# Power.net
KiCad netlist of a schematic drawn in Altium Designer
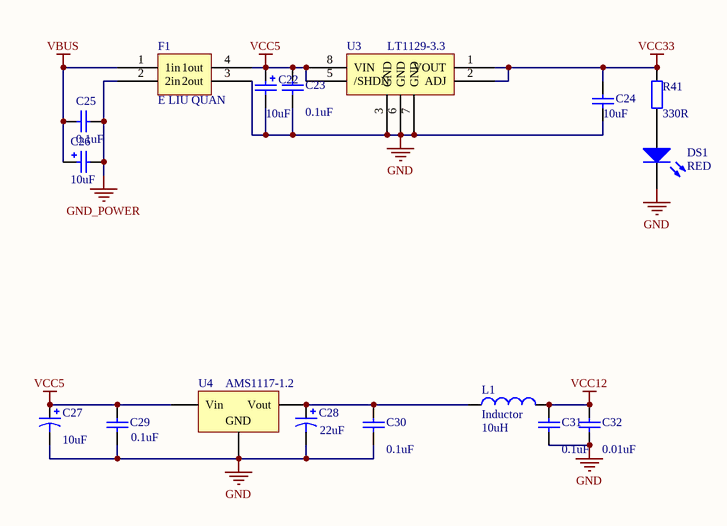
[diagram p0: Power.SchDoc]

(export (version "E")
  (design (tool "Eeschema 10.0.6"))
  (components
    (comp (ref "C22")
      (value "10uF")
      (footprint "cc0603")
      (description "Polarized Capacitor (Radial)")
      (fields (field (name "PUBLISHER") "Altium Limited"))
      (libsource (lib "") (part "Cap Pol1_1"))
    )
    (comp (ref "C23")
      (value "0.1uF")
      (footprint "cc0603")
      (description "Capacitor")
      (fields (field (name "PUBLISHER") "Altium Limited"))
      (libsource (lib "Miscellaneous Devices") (part "Cap"))
    )
    (comp (ref "C24")
      (value "10uF")
      (footprint "cc0603")
      (description "Capacitor")
      (fields (field (name "PUBLISHER") "Altium Limited"))
      (libsource (lib "Miscellaneous Devices") (part "Cap"))
    )
    (comp (ref "C25")
      (value "0.1uF")
      (footprint "cc0603")
      (description "Capacitor")
      (fields (field (name "PUBLISHER") "Altium Limited"))
      (libsource (lib "Miscellaneous Devices") (part "Cap"))
    )
    (comp (ref "C26")
      (value "10uF")
      (footprint "CC6332-2512")
      (description "Polarized Capacitor (Radial)")
      (fields (field (name "PUBLISHER") "Altium Limited"))
      (libsource (lib "") (part "Cap Pol1_1"))
    )
    (comp (ref "C27")
      (value "10uF")
      (footprint "CC6332-2512")
      (description "Polarized Capacitor (Radial)")
      (fields (field (name "PUBLISHER") "Altium Limited"))
      (libsource (lib "Miscellaneous Devices") (part "Cap Pol1"))
    )
    (comp (ref "C28")
      (value "22uF")
      (footprint "CC6332-2512")
      (description "Polarized Capacitor (Radial)")
      (fields (field (name "Comment") "Cap Pol1") (field (name "PUBLISHER") "Altium Limited"))
      (libsource (lib "Miscellaneous Devices") (part "Cap Pol1"))
    )
    (comp (ref "C29")
      (value "0.1uF")
      (footprint "cc0603")
      (description "Capacitor")
      (fields (field (name "PUBLISHER") "Altium Limited"))
      (libsource (lib "Miscellaneous Devices") (part "Cap"))
    )
    (comp (ref "C30")
      (value "0.1uF")
      (footprint "cc0603")
      (description "Capacitor")
      (fields (field (name "PUBLISHER") "Altium Limited"))
      (libsource (lib "Miscellaneous Devices") (part "Cap"))
    )
    (comp (ref "C31")
      (value "0.1uF")
      (footprint "cc0603")
      (description "Capacitor")
      (fields (field (name "PUBLISHER") "Altium Limited"))
      (libsource (lib "Miscellaneous Devices") (part "Cap"))
    )
    (comp (ref "C32")
      (value "0.01uF")
      (footprint "cc0603")
      (description "Capacitor")
      (fields (field (name "PUBLISHER") "Altium Limited"))
      (libsource (lib "Miscellaneous Devices") (part "Cap"))
    )
    (comp (ref "DS1")
      (value "RED")
      (footprint "CR0805")
      (description "Typical INFRARED GaAs LED")
      (fields (field (name "PUBLISHER") "Altium Limited"))
      (libsource (lib "Miscellaneous Devices") (part "LED0"))
    )
    (comp (ref "F1")
      (value "E LIU QUAN")
      (footprint "L_eliuquan")
      (libsource (lib "E liu quan") (part "E LIU QUAN"))
    )
    (comp (ref "L1")
      (value "Inductor")
      (footprint "CR0603")
      (fields (field (name "ALTIUM_VALUE") "10uH") (field (name "PUBLISHER") "Altium Limited"))
      (libsource (lib "Miscellaneous Devices") (part "Inductor"))
    )
    (comp (ref "R41")
      (value "330R")
      (footprint "CR0603")
      (description "Resistor")
      (fields (field (name "Comment") "Res2") (field (name "PUBLISHER") "Altium Limited"))
      (libsource (lib "Miscellaneous Devices") (part "Res2"))
    )
    (comp (ref "U3")
      (value "LT1129-3.3")
      (footprint "sop8")
      (libsource (lib "LT1129-3.3") (part "LT1129-3.3"))
    )
    (comp (ref "U4")
      (value "Volt Reg")
      (footprint "AS1117")
      (description "Voltage Regulator")
      (fields (field (name "PUBLISHER") "Altium Limited"))
      (libsource (lib "Miscellaneous Devices") (part "Volt Reg"))
    )
  )
  (nets
    (net (code "1") (name "GND") (class "Default")
      (node (ref "C22") (pin "2") (pinfunction "2_2") (pintype "passive"))
      (node (ref "C23") (pin "1") (pinfunction "1_1") (pintype "passive"))
      (node (ref "C24") (pin "1") (pinfunction "1_1") (pintype "passive"))
      (node (ref "C27") (pin "2") (pinfunction "2_2") (pintype "passive"))
      (node (ref "C28") (pin "2") (pinfunction "2_2") (pintype "passive"))
      (node (ref "C29") (pin "1") (pinfunction "1_1") (pintype "passive"))
      (node (ref "C30") (pin "1") (pinfunction "1_1") (pintype "passive"))
      (node (ref "C31") (pin "1") (pinfunction "1_1") (pintype "passive"))
      (node (ref "C32") (pin "1") (pinfunction "1_1") (pintype "passive"))
      (node (ref "DS1") (pin "2") (pinfunction "K_2") (pintype "passive"))
      (node (ref "F1") (pin "3") (pinfunction "2out_3") (pintype "passive"))
      (node (ref "U3") (pin "3") (pinfunction "GND_3") (pintype "passive"))
      (node (ref "U3") (pin "6") (pinfunction "GND_6") (pintype "passive"))
      (node (ref "U3") (pin "7") (pinfunction "GND_7") (pintype "passive"))
      (node (ref "U4") (pin "1") (pinfunction "GND_1") (pintype "passive"))
    )
    (net (code "2") (name "GND_POWER") (class "Default")
      (node (ref "C25") (pin "1") (pinfunction "1_1") (pintype "passive"))
      (node (ref "C26") (pin "2") (pinfunction "2_2") (pintype "passive"))
      (node (ref "F1") (pin "2") (pinfunction "2in_2") (pintype "passive"))
    )
    (net (code "3") (name "Net-(DS1-A)") (class "Default")
      (node (ref "DS1") (pin "1") (pinfunction "A_1") (pintype "passive"))
      (node (ref "R41") (pin "1") (pinfunction "1_1") (pintype "passive"))
    )
    (net (code "4") (name "Net-(U4-Vout)") (class "Default")
      (node (ref "C28") (pin "1") (pinfunction "1_1") (pintype "passive"))
      (node (ref "C30") (pin "2") (pinfunction "2_2") (pintype "passive"))
      (node (ref "L1") (pin "1") (pinfunction "1_1") (pintype "passive"))
      (node (ref "U4") (pin "2") (pinfunction "Vout_2") (pintype "passive"))
    )
    (net (code "5") (name "VBUS") (class "Default")
      (node (ref "C25") (pin "2") (pinfunction "2_2") (pintype "passive"))
      (node (ref "C26") (pin "1") (pinfunction "1_1") (pintype "passive"))
      (node (ref "F1") (pin "1") (pinfunction "1in_1") (pintype "passive"))
    )
    (net (code "6") (name "VCC5") (class "Default")
      (node (ref "C22") (pin "1") (pinfunction "1_1") (pintype "passive"))
      (node (ref "C23") (pin "2") (pinfunction "2_2") (pintype "passive"))
      (node (ref "C27") (pin "1") (pinfunction "1_1") (pintype "passive"))
      (node (ref "C29") (pin "2") (pinfunction "2_2") (pintype "passive"))
      (node (ref "F1") (pin "4") (pinfunction "1out_4") (pintype "passive"))
      (node (ref "U3") (pin "5") (pinfunction "/SHDN_5") (pintype "passive"))
      (node (ref "U3") (pin "8") (pinfunction "VIN_8") (pintype "passive"))
      (node (ref "U4") (pin "3") (pinfunction "Vin_3") (pintype "passive"))
    )
    (net (code "7") (name "VCC12") (class "Default")
      (node (ref "C31") (pin "2") (pinfunction "2_2") (pintype "passive"))
      (node (ref "C32") (pin "2") (pinfunction "2_2") (pintype "passive"))
      (node (ref "L1") (pin "2") (pinfunction "2_2") (pintype "passive"))
    )
    (net (code "8") (name "VCC33") (class "Default")
      (node (ref "C24") (pin "2") (pinfunction "2_2") (pintype "passive"))
      (node (ref "R41") (pin "2") (pinfunction "2_2") (pintype "passive"))
      (node (ref "U3") (pin "1") (pinfunction "VOUT_1") (pintype "passive"))
      (node (ref "U3") (pin "2") (pinfunction "ADJ_2") (pintype "passive"))
    )
  )
)
